# RF.net
KiCad netlist of a schematic drawn in Altium Designer
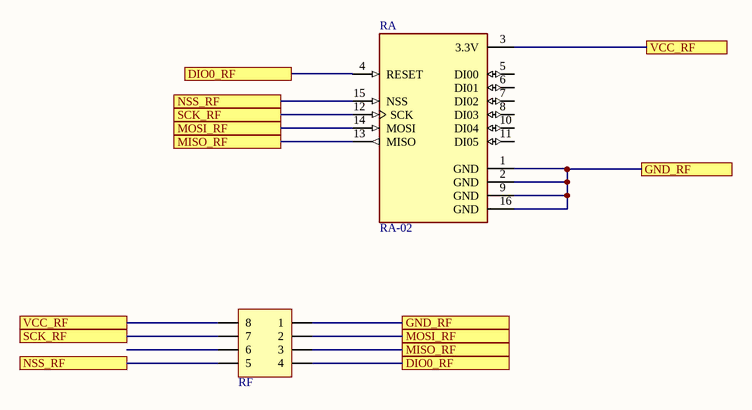
[diagram p0: RF.SchDoc]

(export (version "E")
  (design (tool "Eeschema 10.0.6"))
  (components
    (comp (ref "RA")
      (value "RA-02")
      (footprint "RA-02")
      (fields (field (name "MF") "Ai-Thinker"))
      (libsource (lib "RA-02") (part "RA-02"))
    )
    (comp (ref "RF")
      (value "JP 2x4 2.54")
      (footprint "JP 2x4 DT")
      (description "Cắm")
      (libsource (lib "Altium_Lib_by_KhueNguyenCreator") (part "JP 2x4 2.54 Duc Thang"))
    )
  )
  (nets
    (net (code "1") (name "/DIO0_RF") (class "Default")
      (node (ref "RA") (pin "4") (pinfunction "RESET_4") (pintype "input"))
      (node (ref "RF") (pin "4") (pinfunction "4_4") (pintype "passive"))
    )
    (net (code "2") (name "/GND_RF") (class "Default")
      (node (ref "RA") (pin "1") (pinfunction "GND_1") (pintype "power_in"))
      (node (ref "RA") (pin "16") (pinfunction "GND_16") (pintype "power_in"))
      (node (ref "RA") (pin "2") (pinfunction "GND_2") (pintype "power_in"))
      (node (ref "RA") (pin "9") (pinfunction "GND_9") (pintype "power_in"))
      (node (ref "RF") (pin "1") (pinfunction "1_1") (pintype "passive"))
    )
    (net (code "3") (name "/MISO_RF") (class "Default")
      (node (ref "RA") (pin "13") (pinfunction "MISO_13") (pintype "output"))
      (node (ref "RF") (pin "3") (pinfunction "3_3") (pintype "passive"))
    )
    (net (code "4") (name "/MOSI_RF") (class "Default")
      (node (ref "RA") (pin "14") (pinfunction "MOSI_14") (pintype "input"))
      (node (ref "RF") (pin "2") (pinfunction "2_2") (pintype "passive"))
    )
    (net (code "5") (name "/NSS_RF") (class "Default")
      (node (ref "RA") (pin "15") (pinfunction "NSS_15") (pintype "input"))
      (node (ref "RF") (pin "5") (pinfunction "5_5") (pintype "passive"))
    )
    (net (code "6") (name "/SCK_RF") (class "Default")
      (node (ref "RA") (pin "12") (pinfunction "SCK_12") (pintype "input"))
      (node (ref "RF") (pin "7") (pinfunction "7_7") (pintype "passive"))
    )
    (net (code "7") (name "/VCC_RF") (class "Default")
      (node (ref "RA") (pin "3") (pinfunction "3.3V_3") (pintype "power_in"))
      (node (ref "RF") (pin "8") (pinfunction "8_8") (pintype "passive"))
    )
    (net (code "8") (name "unconnected-(RA-DI00-Pad5)") (class "Default")
      (node (ref "RA") (pin "5") (pinfunction "DI00_5") (pintype "bidirectional"))
    )
    (net (code "9") (name "unconnected-(RA-DI01-Pad6)") (class "Default")
      (node (ref "RA") (pin "6") (pinfunction "DI01_6") (pintype "bidirectional"))
    )
    (net (code "10") (name "unconnected-(RA-DI02-Pad7)") (class "Default")
      (node (ref "RA") (pin "7") (pinfunction "DI02_7") (pintype "bidirectional"))
    )
    (net (code "11") (name "unconnected-(RA-DI03-Pad8)") (class "Default")
      (node (ref "RA") (pin "8") (pinfunction "DI03_8") (pintype "bidirectional"))
    )
    (net (code "12") (name "unconnected-(RA-DI04-Pad10)") (class "Default")
      (node (ref "RA") (pin "10") (pinfunction "DI04_10") (pintype "bidirectional"))
    )
    (net (code "13") (name "unconnected-(RA-DI05-Pad11)") (class "Default")
      (node (ref "RA") (pin "11") (pinfunction "DI05_11") (pintype "bidirectional"))
    )
    (net (code "14") (name "unconnected-(RF-Pad6)") (class "Default")
      (node (ref "RF") (pin "6") (pinfunction "6_6") (pintype "passive"))
    )
  )
)
